# Taillight.net
KiCad netlist of a schematic drawn in Altium Designer
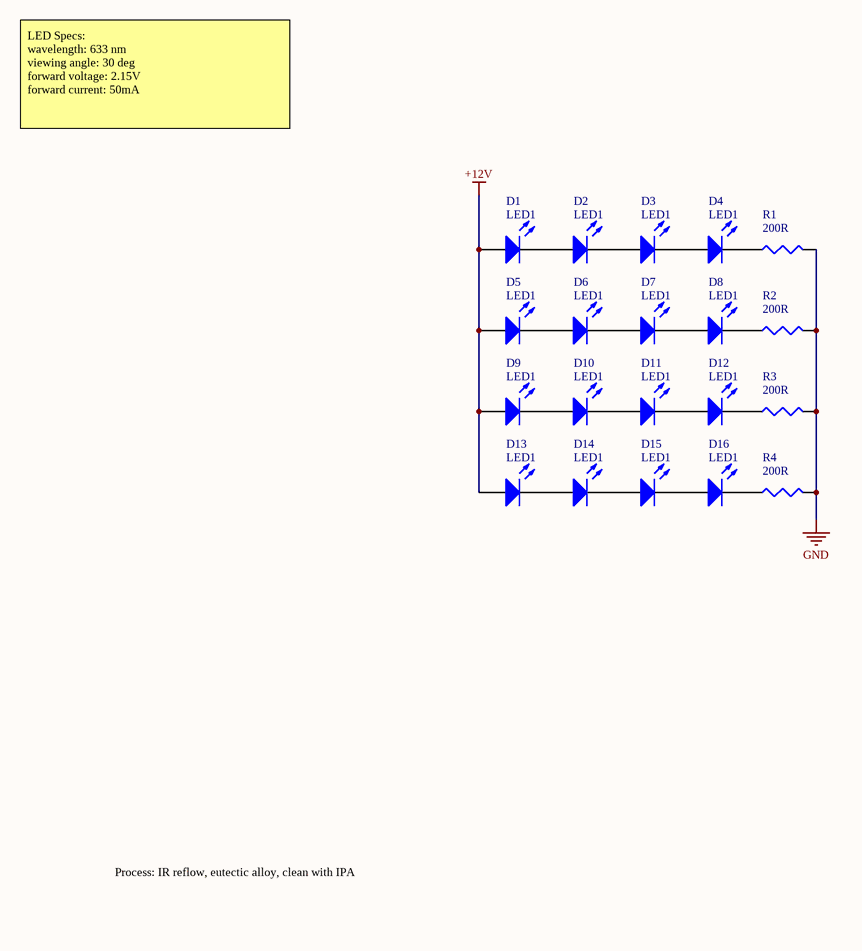
[diagram p0: Taillight.SchDoc]

(export (version "E")
  (design (tool "Eeschema 10.0.6"))
  (components
    (comp (ref "D1")
      (value "LED1")
      (footprint "PLCC-4-1-LED")
      (description "LS E63F-DBFA-1 Red Topled")
      (fields (field (name "PUBLISHER") "Altium Limited"))
      (libsource (lib "Miscellaneous Devices") (part "LED1"))
    )
    (comp (ref "D2")
      (value "LED1")
      (footprint "PLCC-4-1-LED")
      (description "LS E63F-DBFA-1 Red Topled")
      (fields (field (name "PUBLISHER") "Altium Limited"))
      (libsource (lib "Miscellaneous Devices") (part "LED1"))
    )
    (comp (ref "D3")
      (value "LED1")
      (footprint "PLCC-4-1-LED")
      (description "LS E63F-DBFA-1 Red Topled")
      (fields (field (name "PUBLISHER") "Altium Limited"))
      (libsource (lib "Miscellaneous Devices") (part "LED1"))
    )
    (comp (ref "D4")
      (value "LED1")
      (footprint "PLCC-4-1-LED")
      (description "LS E63F-DBFA-1 Red Topled")
      (fields (field (name "PUBLISHER") "Altium Limited"))
      (libsource (lib "Miscellaneous Devices") (part "LED1"))
    )
    (comp (ref "D5")
      (value "LED1")
      (footprint "PLCC-4-1-LED")
      (description "LS E63F-DBFA-1 Red Topled")
      (fields (field (name "PUBLISHER") "Altium Limited"))
      (libsource (lib "Miscellaneous Devices") (part "LED1"))
    )
    (comp (ref "D6")
      (value "LED1")
      (footprint "PLCC-4-1-LED")
      (description "LS E63F-DBFA-1 Red Topled")
      (fields (field (name "PUBLISHER") "Altium Limited"))
      (libsource (lib "Miscellaneous Devices") (part "LED1"))
    )
    (comp (ref "D7")
      (value "LED1")
      (footprint "PLCC-4-1-LED")
      (description "LS E63F-DBFA-1 Red Topled")
      (fields (field (name "PUBLISHER") "Altium Limited"))
      (libsource (lib "Miscellaneous Devices") (part "LED1"))
    )
    (comp (ref "D8")
      (value "LED1")
      (footprint "PLCC-4-1-LED")
      (description "LS E63F-DBFA-1 Red Topled")
      (fields (field (name "PUBLISHER") "Altium Limited"))
      (libsource (lib "Miscellaneous Devices") (part "LED1"))
    )
    (comp (ref "D9")
      (value "LED1")
      (footprint "PLCC-4-1-LED")
      (description "LS E63F-DBFA-1 Red Topled")
      (fields (field (name "PUBLISHER") "Altium Limited"))
      (libsource (lib "Miscellaneous Devices") (part "LED1"))
    )
    (comp (ref "D10")
      (value "LED1")
      (footprint "PLCC-4-1-LED")
      (description "LS E63F-DBFA-1 Red Topled")
      (fields (field (name "PUBLISHER") "Altium Limited"))
      (libsource (lib "Miscellaneous Devices") (part "LED1"))
    )
    (comp (ref "D11")
      (value "LED1")
      (footprint "PLCC-4-1-LED")
      (description "LS E63F-DBFA-1 Red Topled")
      (fields (field (name "PUBLISHER") "Altium Limited"))
      (libsource (lib "Miscellaneous Devices") (part "LED1"))
    )
    (comp (ref "D12")
      (value "LED1")
      (footprint "PLCC-4-1-LED")
      (description "LS E63F-DBFA-1 Red Topled")
      (fields (field (name "PUBLISHER") "Altium Limited"))
      (libsource (lib "Miscellaneous Devices") (part "LED1"))
    )
    (comp (ref "D13")
      (value "LED1")
      (footprint "PLCC-4-1-LED")
      (description "LS E63F-DBFA-1 Red Topled")
      (fields (field (name "PUBLISHER") "Altium Limited"))
      (libsource (lib "Miscellaneous Devices") (part "LED1"))
    )
    (comp (ref "D14")
      (value "LED1")
      (footprint "PLCC-4-1-LED")
      (description "LS E63F-DBFA-1 Red Topled")
      (fields (field (name "PUBLISHER") "Altium Limited"))
      (libsource (lib "Miscellaneous Devices") (part "LED1"))
    )
    (comp (ref "D15")
      (value "LED1")
      (footprint "PLCC-4-1-LED")
      (description "LS E63F-DBFA-1 Red Topled")
      (fields (field (name "PUBLISHER") "Altium Limited"))
      (libsource (lib "Miscellaneous Devices") (part "LED1"))
    )
    (comp (ref "D16")
      (value "LED1")
      (footprint "PLCC-4-1-LED")
      (description "LS E63F-DBFA-1 Red Topled")
      (fields (field (name "PUBLISHER") "Altium Limited"))
      (libsource (lib "Miscellaneous Devices") (part "LED1"))
    )
    (comp (ref "R1")
      (value "200R")
      (footprint "1210")
      (description "Resistor")
      (fields (field (name "Comment") "Comment") (field (name "PUBLISHER") "Altium Limited"))
      (libsource (lib "Miscellaneous Devices") (part "Res3"))
    )
    (comp (ref "R2")
      (value "200R")
      (footprint "1210")
      (description "Resistor")
      (fields (field (name "Comment") "Comment") (field (name "PUBLISHER") "Altium Limited"))
      (libsource (lib "Miscellaneous Devices") (part "Res3"))
    )
    (comp (ref "R3")
      (value "200R")
      (footprint "1210")
      (description "Resistor")
      (fields (field (name "Comment") "Comment") (field (name "PUBLISHER") "Altium Limited"))
      (libsource (lib "Miscellaneous Devices") (part "Res3"))
    )
    (comp (ref "R4")
      (value "200R")
      (footprint "1210")
      (description "Resistor")
      (fields (field (name "Comment") "Comment") (field (name "PUBLISHER") "Altium Limited"))
      (libsource (lib "Miscellaneous Devices") (part "Res3"))
    )
  )
  (nets
    (net (code "1") (name "+12V") (class "Default")
      (node (ref "D1") (pin "1") (pinfunction "1_1") (pintype "passive"))
      (node (ref "D13") (pin "1") (pinfunction "1_1") (pintype "passive"))
      (node (ref "D5") (pin "1") (pinfunction "1_1") (pintype "passive"))
      (node (ref "D9") (pin "1") (pinfunction "1_1") (pintype "passive"))
    )
    (net (code "2") (name "GND") (class "Default")
      (node (ref "R1") (pin "2") (pinfunction "2_2") (pintype "passive"))
      (node (ref "R2") (pin "2") (pinfunction "2_2") (pintype "passive"))
      (node (ref "R3") (pin "2") (pinfunction "2_2") (pintype "passive"))
      (node (ref "R4") (pin "2") (pinfunction "2_2") (pintype "passive"))
    )
    (net (code "3") (name "Net-(D1-Pad2)") (class "Default")
      (node (ref "D1") (pin "2") (pinfunction "2_2") (pintype "passive"))
      (node (ref "D2") (pin "1") (pinfunction "1_1") (pintype "passive"))
    )
    (net (code "4") (name "Net-(D2-Pad2)") (class "Default")
      (node (ref "D2") (pin "2") (pinfunction "2_2") (pintype "passive"))
      (node (ref "D3") (pin "1") (pinfunction "1_1") (pintype "passive"))
    )
    (net (code "5") (name "Net-(D3-Pad2)") (class "Default")
      (node (ref "D3") (pin "2") (pinfunction "2_2") (pintype "passive"))
      (node (ref "D4") (pin "1") (pinfunction "1_1") (pintype "passive"))
    )
    (net (code "6") (name "Net-(D4-Pad2)") (class "Default")
      (node (ref "D4") (pin "2") (pinfunction "2_2") (pintype "passive"))
      (node (ref "R1") (pin "1") (pinfunction "1_1") (pintype "passive"))
    )
    (net (code "7") (name "Net-(D5-Pad2)") (class "Default")
      (node (ref "D5") (pin "2") (pinfunction "2_2") (pintype "passive"))
      (node (ref "D6") (pin "1") (pinfunction "1_1") (pintype "passive"))
    )
    (net (code "8") (name "Net-(D6-Pad2)") (class "Default")
      (node (ref "D6") (pin "2") (pinfunction "2_2") (pintype "passive"))
      (node (ref "D7") (pin "1") (pinfunction "1_1") (pintype "passive"))
    )
    (net (code "9") (name "Net-(D7-Pad2)") (class "Default")
      (node (ref "D7") (pin "2") (pinfunction "2_2") (pintype "passive"))
      (node (ref "D8") (pin "1") (pinfunction "1_1") (pintype "passive"))
    )
    (net (code "10") (name "Net-(D8-Pad2)") (class "Default")
      (node (ref "D8") (pin "2") (pinfunction "2_2") (pintype "passive"))
      (node (ref "R2") (pin "1") (pinfunction "1_1") (pintype "passive"))
    )
    (net (code "11") (name "Net-(D10-Pad1)") (class "Default")
      (node (ref "D10") (pin "1") (pinfunction "1_1") (pintype "passive"))
      (node (ref "D9") (pin "2") (pinfunction "2_2") (pintype "passive"))
    )
    (net (code "12") (name "Net-(D10-Pad2)") (class "Default")
      (node (ref "D10") (pin "2") (pinfunction "2_2") (pintype "passive"))
      (node (ref "D11") (pin "1") (pinfunction "1_1") (pintype "passive"))
    )
    (net (code "13") (name "Net-(D11-Pad2)") (class "Default")
      (node (ref "D11") (pin "2") (pinfunction "2_2") (pintype "passive"))
      (node (ref "D12") (pin "1") (pinfunction "1_1") (pintype "passive"))
    )
    (net (code "14") (name "Net-(D12-Pad2)") (class "Default")
      (node (ref "D12") (pin "2") (pinfunction "2_2") (pintype "passive"))
      (node (ref "R3") (pin "1") (pinfunction "1_1") (pintype "passive"))
    )
    (net (code "15") (name "Net-(D13-Pad2)") (class "Default")
      (node (ref "D13") (pin "2") (pinfunction "2_2") (pintype "passive"))
      (node (ref "D14") (pin "1") (pinfunction "1_1") (pintype "passive"))
    )
    (net (code "16") (name "Net-(D14-Pad2)") (class "Default")
      (node (ref "D14") (pin "2") (pinfunction "2_2") (pintype "passive"))
      (node (ref "D15") (pin "1") (pinfunction "1_1") (pintype "passive"))
    )
    (net (code "17") (name "Net-(D15-Pad2)") (class "Default")
      (node (ref "D15") (pin "2") (pinfunction "2_2") (pintype "passive"))
      (node (ref "D16") (pin "1") (pinfunction "1_1") (pintype "passive"))
    )
    (net (code "18") (name "Net-(D16-Pad2)") (class "Default")
      (node (ref "D16") (pin "2") (pinfunction "2_2") (pintype "passive"))
      (node (ref "R4") (pin "1") (pinfunction "1_1") (pintype "passive"))
    )
  )
)
